# RF_AMP.net
KiCad netlist of a schematic drawn in Altium Designer
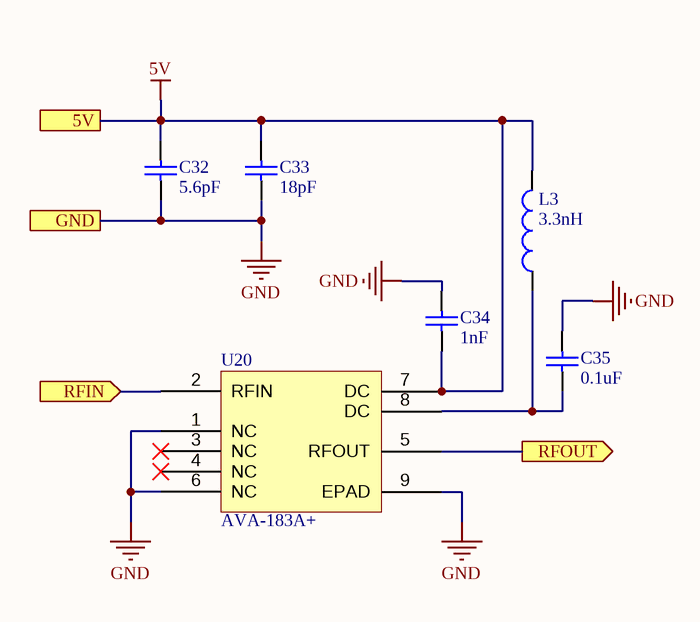
[diagram p0: RF_AMP.SchDoc]

(export (version "E")
  (design (tool "Eeschema 10.0.6"))
  (components
    (comp (ref "C32")
      (value "5.6pF")
      (footprint "SMD-0402")
      (description "Ceramic Capacitor 0402")
      (libsource (lib "LCR") (part "CAP0402"))
    )
    (comp (ref "C33")
      (value "18pF")
      (footprint "SMD-0402")
      (description "Ceramic Capacitor 0402")
      (libsource (lib "LCR") (part "CAP0402"))
    )
    (comp (ref "C34")
      (value "1nF")
      (footprint "SMD-0402")
      (description "Ceramic Capacitor 0402")
      (libsource (lib "LCR") (part "CAP0402"))
    )
    (comp (ref "C35")
      (value "0.1uF")
      (footprint "SMD-0402")
      (description "Ceramic Capacitor 0402")
      (libsource (lib "LCR") (part "CAP0402"))
    )
    (comp (ref "L3")
      (value "3.3nH")
      (footprint "SMD-0805")
      (description "Inductor 0805")
      (libsource (lib "LCR") (part "L0805"))
    )
    (comp (ref "U20")
      (value "AVA-183A+")
      (footprint "AVA-183A+ QFN")
      (description "Wideband, Microwave, Monolithic Amplifier, 50Ω, 5 to 18 GHz")
      (libsource (lib "FullyDigital") (part "AVA-183A+"))
    )
  )
  (nets
    (net (code "1") (name "/RFIN") (class "Default")
      (node (ref "U20") (pin "2") (pinfunction "RFIN_2") (pintype "passive"))
    )
    (net (code "2") (name "/RFOUT") (class "Default")
      (node (ref "U20") (pin "5") (pinfunction "RFOUT_5") (pintype "passive"))
    )
    (net (code "3") (name "5V") (class "Default")
      (node (ref "C32") (pin "2") (pinfunction "2_2") (pintype "passive"))
      (node (ref "C33") (pin "2") (pinfunction "2_2") (pintype "passive"))
      (node (ref "C34") (pin "1") (pinfunction "1_1") (pintype "passive"))
      (node (ref "L3") (pin "2") (pinfunction "2_2") (pintype "passive"))
      (node (ref "U20") (pin "7") (pinfunction "DC_7") (pintype "passive"))
    )
    (net (code "4") (name "GND") (class "Default")
      (node (ref "C32") (pin "1") (pinfunction "1_1") (pintype "passive"))
      (node (ref "C33") (pin "1") (pinfunction "1_1") (pintype "passive"))
      (node (ref "C34") (pin "2") (pinfunction "2_2") (pintype "passive"))
      (node (ref "C35") (pin "2") (pinfunction "2_2") (pintype "passive"))
      (node (ref "U20") (pin "1") (pinfunction "NC_1") (pintype "passive"))
      (node (ref "U20") (pin "6") (pinfunction "NC_6") (pintype "passive"))
      (node (ref "U20") (pin "9") (pinfunction "EPAD_9") (pintype "passive"))
    )
    (net (code "5") (name "Net-(C35-Pad1)") (class "Default")
      (node (ref "C35") (pin "1") (pinfunction "1_1") (pintype "passive"))
      (node (ref "L3") (pin "1") (pinfunction "1_1") (pintype "passive"))
      (node (ref "U20") (pin "8") (pinfunction "DC_8") (pintype "passive"))
    )
    (net (code "6") (name "unconnected-(U20-NC-Pad3)") (class "Default")
      (node (ref "U20") (pin "3") (pinfunction "NC_3") (pintype "passive+no_connect"))
    )
    (net (code "7") (name "unconnected-(U20-NC-Pad4)") (class "Default")
      (node (ref "U20") (pin "4") (pinfunction "NC_4") (pintype "passive+no_connect"))
    )
  )
)
